# 1_EVB_A32QS1_RFRG_Schematic.net
KiCad netlist of a schematic drawn in Altium Designer
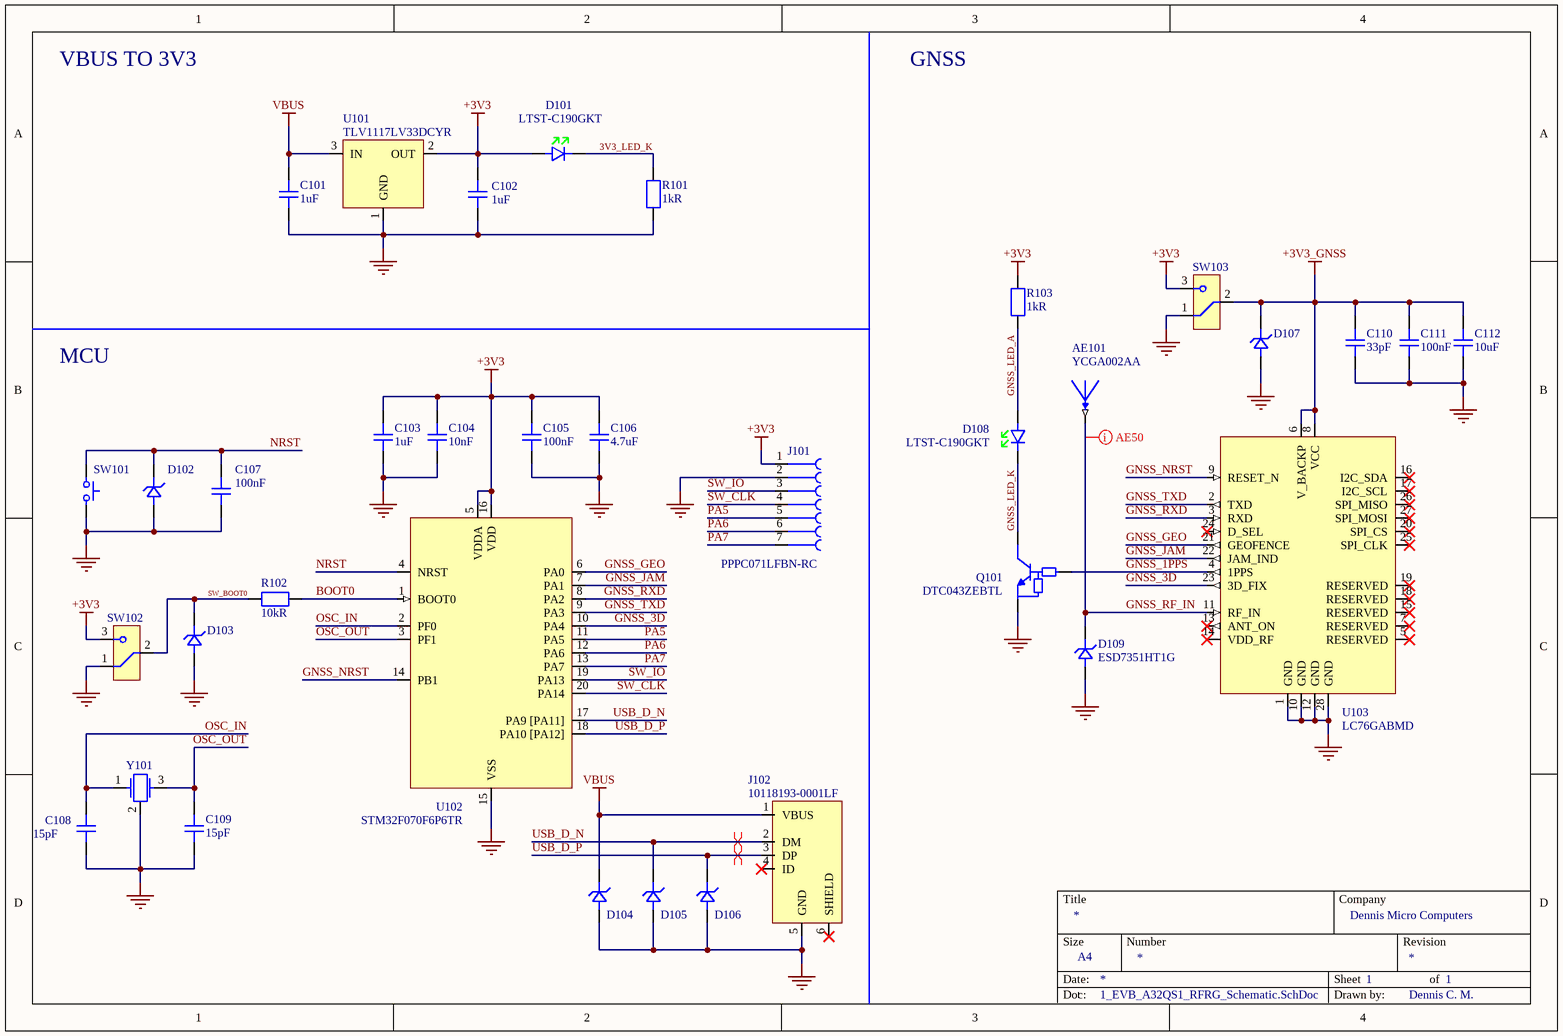
[diagram p0: 1_EVB_A32QS1_RFRG_Schematic.SchDoc]

(export (version "E")
  (design (tool "Eeschema 10.0.6"))
  (components
    (comp (ref "AE101")
      (value "YCGA002AA")
      (footprint "AE_Quectel_YCGA002AA")
      (description "Antenna Module Linear 1602MHz")
      (fields (field (name "MANUFACTURER") "Quectel"))
      (libsource (lib "Dennis Micro Computers") (part "AE_Receiver"))
    )
    (comp (ref "C101")
      (value "1uF")
      (footprint "C_Yageo_CC_0402_A")
      (description "Multilayer Ceramic Capacitor, 1 uF, 50 V, ± 10%, X5R, 0402 [1005 Metric]")
      (fields (field (name "TOLERANCE") "20%") (field (name "LCSC PART NUMBER") "C113791"))
      (libsource (lib "Dennis Micro Computers") (part "C"))
    )
    (comp (ref "C102")
      (value "1uF")
      (footprint "C_Yageo_CC_0402_A")
      (description "Multilayer Ceramic Capacitor, 1 uF, 50 V, ± 10%, X5R, 0402 [1005 Metric]")
      (fields (field (name "TOLERANCE") "20%") (field (name "LCSC PART NUMBER") "C113791"))
      (libsource (lib "Dennis Micro Computers") (part "C"))
    )
    (comp (ref "C103")
      (value "1uF")
      (footprint "C_Yageo_CC_0402_A")
      (description "Multilayer Ceramic Capacitor, 1 uF, 50 V, ± 10%, X5R, 0402 [1005 Metric]")
      (fields (field (name "TOLERANCE") "20%") (field (name "LCSC PART NUMBER") "C113791"))
      (libsource (lib "Dennis Micro Computers") (part "C"))
    )
    (comp (ref "C104")
      (value "10nF")
      (footprint "C_Yageo_CC_0402_A")
      (description "Multilayer Ceramic Capacitor, 0.01 uF, 16 V, ± 10%, X7R, 0402 [1005 Metric]")
      (fields (field (name "TOLERANCE") "10%") (field (name "Comment") "CC0402KRX7R7BB103"))
      (libsource (lib "Dennis Micro Computers") (part "C"))
    )
    (comp (ref "C105")
      (value "100nF")
      (footprint "C_Samsung_CL_0402_A")
      (description "Multilayer Ceramic Capacitor, 0.1 uF, 10 V, ± 10%, X7R, 0402 [1005 Metric]")
      (fields (field (name "TOLERANCE") "10%") (field (name "Comment") "CL05B104KP5NNNC"))
      (libsource (lib "Dennis Micro Computers") (part "C"))
    )
    (comp (ref "C106")
      (value "4.7uF")
      (footprint "C_Samsung_CL_0402_A")
      (description "Multilayer Ceramic Capacitor, 4.7 uF, 10 V, ± 20%, X5R, 0402 [1005 Metric]")
      (fields (field (name "TOLERANCE") "20%") (field (name "Comment") "CL05A475MP5NRNC"))
      (libsource (lib "Dennis Micro Computers") (part "C"))
    )
    (comp (ref "C107")
      (value "100nF")
      (footprint "C_Samsung_CL_0402_A")
      (description "Multilayer Ceramic Capacitor, 0.1 uF, 10 V, ± 10%, X7R, 0402 [1005 Metric]")
      (fields (field (name "TOLERANCE") "10%") (field (name "Comment") "CL05B104KP5NNNC"))
      (libsource (lib "Dennis Micro Computers") (part "C"))
    )
    (comp (ref "C108")
      (value "15pF")
      (footprint "C_Yageo_CC_0402_A")
      (description "Multilayer Ceramic Capacitor, 15 pF, 10 V, ± 5%, X7R, 0402 [1005 Metric]")
      (fields (field (name "TOLERANCE") "5%") (field (name "VOLTAGE") "50V"))
      (libsource (lib "Dennis Micro Computers") (part "C"))
    )
    (comp (ref "C109")
      (value "15pF")
      (footprint "C_Yageo_CC_0402_A")
      (description "Multilayer Ceramic Capacitor, 15 pF, 10 V, ± 5%, X7R, 0402 [1005 Metric]")
      (fields (field (name "TOLERANCE") "5%") (field (name "VOLTAGE") "50V"))
      (libsource (lib "Dennis Micro Computers") (part "C"))
    )
    (comp (ref "C110")
      (value "33pF")
      (footprint "C_Samsung_CL_0402_A")
      (description "Multilayer Ceramic Capacitor, 33 pF, 50 V, ± 5%, C0G (NP0), 0402 [1005 Metric]")
      (fields (field (name "VOLTAGE") "50V") (field (name "TOLERANCE") "5%"))
      (libsource (lib "Dennis Micro Computers") (part "C"))
    )
    (comp (ref "C111")
      (value "100nF")
      (footprint "C_Samsung_CL_0402_A")
      (description "Multilayer Ceramic Capacitor, 0.1 uF, 10 V, ± 10%, X7R, 0402 [1005 Metric]")
      (fields (field (name "TOLERANCE") "10%") (field (name "Comment") "CL05B104KP5NNNC"))
      (libsource (lib "Dennis Micro Computers") (part "C"))
    )
    (comp (ref "C112")
      (value "10uF")
      (footprint "C_Samsung_CL_0805_A")
      (description "Multilayer Ceramic Capacitor, 10 uF, 16 V, ± 10%, X5R, 0805 [2012 Metric]")
      (fields (field (name "TOLERANCE") "10%") (field (name "VOLTAGE") "16V"))
      (libsource (lib "Dennis Micro Computers") (part "C"))
    )
    (comp (ref "D101")
      (value "LTST-C190GKT")
      (footprint "D_LED_Lite-On_Green_0603_A")
      (description "LED Uni-Color Green 565nm 2-Pin Chip LED T/R")
      (fields (field (name "VOLTAGE") "2V"))
      (libsource (lib "Dennis Micro Computers") (part "D_LED_Green"))
    )
    (comp (ref "D102")
      (value "D5V0F1U2S9-7")
      (footprint "D_TVS_Uni_Diodes_SOD-923_B")
      (description "Diode TVS Dual Uni-Dir 5.5V 250000W 2-Pin SOD-923 T/R")
      (libsource (lib "Dennis Micro Computers") (part "D_TVS_Uni"))
    )
    (comp (ref "D103")
      (value "D5V0F1U2S9-7")
      (footprint "D_TVS_Uni_Diodes_SOD-923_B")
      (description "Diode TVS Dual Uni-Dir 5.5V 250000W 2-Pin SOD-923 T/R")
      (libsource (lib "Dennis Micro Computers") (part "D_TVS_Uni"))
    )
    (comp (ref "D104")
      (value "D5V0F1U2S9-7")
      (footprint "D_TVS_Uni_Diodes_SOD-923_B")
      (description "Diode TVS Dual Uni-Dir 5.5V 250000W 2-Pin SOD-923 T/R")
      (libsource (lib "Dennis Micro Computers") (part "D_TVS_Uni"))
    )
    (comp (ref "D105")
      (value "D5V0F1U2S9-7")
      (footprint "D_TVS_Uni_Diodes_SOD-923_B")
      (description "Diode TVS Dual Uni-Dir 5.5V 250000W 2-Pin SOD-923 T/R")
      (libsource (lib "Dennis Micro Computers") (part "D_TVS_Uni"))
    )
    (comp (ref "D106")
      (value "D5V0F1U2S9-7")
      (footprint "D_TVS_Uni_Diodes_SOD-923_B")
      (description "Diode TVS Dual Uni-Dir 5.5V 250000W 2-Pin SOD-923 T/R")
      (libsource (lib "Dennis Micro Computers") (part "D_TVS_Uni"))
    )
    (comp (ref "D107")
      (value "D5V0F1U2S9-7")
      (footprint "D_TVS_Uni_Diodes_SOD-923_B")
      (description "Diode TVS Dual Uni-Dir 5.5V 250000W 2-Pin SOD-923 T/R")
      (libsource (lib "Dennis Micro Computers") (part "D_TVS_Uni"))
    )
    (comp (ref "D108")
      (value "LTST-C190GKT")
      (footprint "D_LED_Lite-On_Green_0603_A")
      (description "LED Uni-Color Green 565nm 2-Pin Chip LED T/R")
      (fields (field (name "VOLTAGE") "2V"))
      (libsource (lib "Dennis Micro Computers") (part "D_LED_Green"))
    )
    (comp (ref "D109")
      (value "ESD7351HT1G")
      (footprint "D_TVS_Uni_Onsemi_SOD-323")
      (description "TVSDIODE3.3VWMSOD-323")
      (libsource (lib "Dennis Micro Computers") (part "D_TVS_Uni"))
    )
    (comp (ref "J101")
      (value "PPPC071LFBN-RC")
      (footprint "J_Sullins_01x07_Socket_2.54mm")
      (description "Conn Hdr 7POS 0.1 Gold Pcb")
      (libsource (lib "Dennis Micro Computers") (part "J_01x07_Socket"))
    )
    (comp (ref "J102")
      (value "10118193-0001LF")
      (footprint "J_USB_Micro-B_Amphenol_10118193-0001LF")
      (description "Usb Connector, 5 Contact(S), Female, Right Angle, Surface Mount Terminal, Locking, Receptacle")
      (libsource (lib "Dennis Micro Computers") (part "J_USB2_B_Micro"))
    )
    (comp (ref "Q101")
      (value "DTC043ZEBTL")
      (footprint "Q_Rohm_SOT-416FL_B")
      (description "TRANS PREBIAS NPN 50V EMT3F")
      (libsource (lib "Dennis Micro Computers") (part "Q_BRT_NPN"))
    )
    (comp (ref "R101")
      (value "1kR")
      (footprint "R_Yageo_RCL_0402_A")
      (description "SMD Chip Resistor, 1 kOhm, ± 1%, 62.5 mW, 0402 [1005 Metric], Thick Film, General Purpose")
      (fields (field (name "TOLERANCE") "1%") (field (name "Comment") "RC0402FR-071KL"))
      (libsource (lib "Dennis Micro Computers") (part "R"))
    )
    (comp (ref "R102")
      (value "10kR")
      (footprint "R_Yageo_RCL_0402_A")
      (description "SMD Chip Resistor, 10 kOhm, ± 1%, 62.5 mW, 0402 [1005 Metric], Thick Film, General Purpose")
      (fields (field (name "TOLERANCE") "1%") (field (name "Comment") "RC0402FR-0710KL"))
      (libsource (lib "Dennis Micro Computers") (part "R"))
    )
    (comp (ref "R103")
      (value "1kR")
      (footprint "R_Yageo_RCL_0402_A")
      (description "SMD Chip Resistor, 1 kOhm, ± 1%, 62.5 mW, 0402 [1005 Metric], Thick Film, General Purpose")
      (fields (field (name "TOLERANCE") "1%") (field (name "Comment") "RC0402FR-071KL"))
      (libsource (lib "Dennis Micro Computers") (part "R"))
    )
    (comp (ref "SW101")
      (value "PTS647SN50SMTR2LFS")
      (footprint "SW_Tactitle_SPST_C&K_PTS647SN50SMTR2LFS")
      (description "Switch Tactile N.O. SPST Round Button Gull Wing 0.05A 12VDC 100000Cycles 0.98N SMD T/R")
      (libsource (lib "Dennis Micro Computers") (part "SW_Tactile_SPST"))
    )
    (comp (ref "SW102")
      (value "JS102011JCQN")
      (footprint "SW_Slide_C&K_JS102011JCQN")
      (description "JS Series Sub-Miniature Slide Switch SPDT On-On Top Slide 0.3A 6VDC J-Lead Surface Mount T/R")
      (libsource (lib "Dennis Micro Computers") (part "SW_Slide_SPDT"))
    )
    (comp (ref "SW103")
      (value "JS102011JCQN")
      (footprint "SW_Slide_C&K_JS102011JCQN")
      (description "JS Series Sub-Miniature Slide Switch SPDT On-On Top Slide 0.3A 6VDC J-Lead Surface Mount T/R")
      (libsource (lib "Dennis Micro Computers") (part "SW_Slide_SPDT"))
    )
    (comp (ref "U101")
      (value "TLV1117LV33DCYR")
      (footprint "U_TI_SOT-223_B")
      (description "LDO Regulator Pos 3.3V 1A 4-Pin(3+Tab) SOT-223 T/R")
      (libsource (lib "Dennis Micro Computers") (part "U_TLV1117LV"))
    )
    (comp (ref "U102")
      (value "STM32F070F6P6TR")
      (footprint "U_ST_TSSOP20_B")
      (description "IC MCU 32BIT 32KB FLASH 20TSSOP")
      (libsource (lib "Dennis Micro Computers") (part "U_STM32F070F6"))
    )
    (comp (ref "U103")
      (value "LC76GABMD")
      (footprint "U_QUECTEL_LC76G")
      (libsource (lib "Dennis Micro Computers") (part "U_LC76G"))
    )
    (comp (ref "Y101")
      (value "ECS-240-12-37B-CKY-TR")
      (footprint "Y_Crystal_GND24_ECS_240-12-37B-CKY-TR")
      (description "Crystal 24MHz ±10ppm (Tol) ±10ppm (Stability) 12pF FUND 50Ohm 4-Pin Mini-CSMD T/R")
      (libsource (lib "Dennis Micro Computers") (part "Y_Crystal_GND24"))
    )
  )
  (nets
    (net (code "1") (name "+3V3") (class "Default")
      (node (ref "C102") (pin "2") (pinfunction "2_2") (pintype "passive"))
      (node (ref "C103") (pin "2") (pinfunction "2_2") (pintype "passive"))
      (node (ref "C104") (pin "2") (pinfunction "2_2") (pintype "passive"))
      (node (ref "C105") (pin "2") (pinfunction "2_2") (pintype "passive"))
      (node (ref "C106") (pin "2") (pinfunction "2_2") (pintype "passive"))
      (node (ref "D101") (pin "2") (pinfunction "2_2") (pintype "passive"))
      (node (ref "J101") (pin "1") (pinfunction "1_1") (pintype "passive"))
      (node (ref "R103") (pin "2") (pinfunction "2_2") (pintype "passive"))
      (node (ref "SW102") (pin "3") (pinfunction "3_3") (pintype "passive"))
      (node (ref "SW103") (pin "3") (pinfunction "3_3") (pintype "passive"))
      (node (ref "U101") (pin "2") (pinfunction "OUT_2") (pintype "power_in"))
      (node (ref "U102") (pin "16") (pinfunction "VDD_16") (pintype "power_in"))
      (node (ref "U102") (pin "5") (pinfunction "VDDA_5") (pintype "power_in"))
    )
    (net (code "2") (name "+3V3_GNSS") (class "Default")
      (node (ref "C110") (pin "2") (pinfunction "2_2") (pintype "passive"))
      (node (ref "C111") (pin "2") (pinfunction "2_2") (pintype "passive"))
      (node (ref "C112") (pin "2") (pinfunction "2_2") (pintype "passive"))
      (node (ref "D107") (pin "1") (pinfunction "1_1") (pintype "passive"))
      (node (ref "SW103") (pin "2") (pinfunction "2_2") (pintype "passive"))
      (node (ref "U103") (pin "6") (pinfunction "V_BACKP_6") (pintype "power_in"))
      (node (ref "U103") (pin "8") (pinfunction "VCC_8") (pintype "power_in"))
    )
    (net (code "3") (name "/3V3_LED_K") (class "Default")
      (node (ref "D101") (pin "1") (pinfunction "1_1") (pintype "passive"))
      (node (ref "R101") (pin "2") (pinfunction "2_2") (pintype "passive"))
    )
    (net (code "4") (name "/BOOT0") (class "Default")
      (node (ref "R102") (pin "2") (pinfunction "2_2") (pintype "passive"))
      (node (ref "U102") (pin "1") (pinfunction "BOOT0_1") (pintype "input"))
    )
    (net (code "5") (name "/GNSS_1PPS") (class "Default")
      (node (ref "Q101") (pin "1") (pinfunction "BASE_1") (pintype "passive"))
      (node (ref "U103") (pin "4") (pinfunction "1PPS_4") (pintype "output"))
    )
    (net (code "6") (name "/GNSS_3D") (class "Default")
      (node (ref "U102") (pin "10") (pinfunction "PA4_10") (pintype "bidirectional"))
      (node (ref "U103") (pin "23") (pinfunction "3D_FIX_23") (pintype "output"))
    )
    (net (code "7") (name "/GNSS_GEO") (class "Default")
      (node (ref "U102") (pin "6") (pinfunction "PA0_6") (pintype "bidirectional"))
      (node (ref "U103") (pin "21") (pinfunction "GEOFENCE_21") (pintype "output"))
    )
    (net (code "8") (name "/GNSS_JAM") (class "Default")
      (node (ref "U102") (pin "7") (pinfunction "PA1_7") (pintype "bidirectional"))
      (node (ref "U103") (pin "22") (pinfunction "JAM_IND_22") (pintype "output"))
    )
    (net (code "9") (name "/GNSS_LED_A") (class "Default")
      (node (ref "D108") (pin "2") (pinfunction "2_2") (pintype "passive"))
      (node (ref "R103") (pin "1") (pinfunction "1_1") (pintype "passive"))
    )
    (net (code "10") (name "/GNSS_LED_K") (class "Default")
      (node (ref "D108") (pin "1") (pinfunction "1_1") (pintype "passive"))
      (node (ref "Q101") (pin "3") (pinfunction "COLLECTOR_3") (pintype "passive"))
    )
    (net (code "11") (name "/GNSS_NRST") (class "Default")
      (node (ref "U102") (pin "14") (pinfunction "PB1_14") (pintype "bidirectional"))
      (node (ref "U103") (pin "9") (pinfunction "RESET_N_9") (pintype "input"))
    )
    (net (code "12") (name "/GNSS_RF_IN") (class "Default")
      (node (ref "AE101") (pin "1") (pinfunction "1_1") (pintype "output"))
      (node (ref "D109") (pin "1") (pinfunction "1_1") (pintype "passive"))
      (node (ref "U103") (pin "11") (pinfunction "RF_IN_11") (pintype "input"))
    )
    (net (code "13") (name "/GNSS_RXD") (class "Default")
      (node (ref "U102") (pin "8") (pinfunction "PA2_8") (pintype "bidirectional"))
      (node (ref "U103") (pin "3") (pinfunction "RXD_3") (pintype "input"))
    )
    (net (code "14") (name "/GNSS_TXD") (class "Default")
      (node (ref "U102") (pin "9") (pinfunction "PA3_9") (pintype "bidirectional"))
      (node (ref "U103") (pin "2") (pinfunction "TXD_2") (pintype "output"))
    )
    (net (code "15") (name "/NRST") (class "Default")
      (node (ref "C107") (pin "2") (pinfunction "2_2") (pintype "passive"))
      (node (ref "D102") (pin "1") (pinfunction "1_1") (pintype "passive"))
      (node (ref "SW101") (pin "1") (pinfunction "1_1") (pintype "passive"))
      (node (ref "U102") (pin "4") (pinfunction "NRST_4") (pintype "bidirectional"))
    )
    (net (code "16") (name "/OSC_IN") (class "Default")
      (node (ref "C108") (pin "2") (pinfunction "2_2") (pintype "passive"))
      (node (ref "U102") (pin "2") (pinfunction "PF0_2") (pintype "bidirectional"))
      (node (ref "Y101") (pin "1") (pinfunction "1_1") (pintype "passive"))
    )
    (net (code "17") (name "/OSC_OUT") (class "Default")
      (node (ref "C109") (pin "2") (pinfunction "2_2") (pintype "passive"))
      (node (ref "U102") (pin "3") (pinfunction "PF1_3") (pintype "bidirectional"))
      (node (ref "Y101") (pin "3") (pinfunction "3_3") (pintype "passive"))
    )
    (net (code "18") (name "/PA5") (class "Default")
      (node (ref "J101") (pin "5") (pinfunction "5_5") (pintype "passive"))
      (node (ref "U102") (pin "11") (pinfunction "PA5_11") (pintype "bidirectional"))
    )
    (net (code "19") (name "/PA6") (class "Default")
      (node (ref "J101") (pin "6") (pinfunction "6_6") (pintype "passive"))
      (node (ref "U102") (pin "12") (pinfunction "PA6_12") (pintype "bidirectional"))
    )
    (net (code "20") (name "/PA7") (class "Default")
      (node (ref "J101") (pin "7") (pinfunction "7_7") (pintype "passive"))
      (node (ref "U102") (pin "13") (pinfunction "PA7_13") (pintype "bidirectional"))
    )
    (net (code "21") (name "/SW_BOOT0") (class "Default")
      (node (ref "D103") (pin "1") (pinfunction "1_1") (pintype "passive"))
      (node (ref "R102") (pin "1") (pinfunction "1_1") (pintype "passive"))
      (node (ref "SW102") (pin "2") (pinfunction "2_2") (pintype "passive"))
    )
    (net (code "22") (name "/SW_CLK") (class "Default")
      (node (ref "J101") (pin "4") (pinfunction "4_4") (pintype "passive"))
      (node (ref "U102") (pin "20") (pinfunction "PA14_20") (pintype "bidirectional"))
    )
    (net (code "23") (name "/SW_IO") (class "Default")
      (node (ref "J101") (pin "3") (pinfunction "3_3") (pintype "passive"))
      (node (ref "U102") (pin "19") (pinfunction "PA13_19") (pintype "bidirectional"))
    )
    (net (code "24") (name "/USB_D_N") (class "Default")
      (node (ref "D105") (pin "1") (pinfunction "1_1") (pintype "passive"))
      (node (ref "J102") (pin "2") (pinfunction "DM_2") (pintype "bidirectional"))
      (node (ref "U102") (pin "17") (pinfunction "PA9_[PA11]_17") (pintype "bidirectional"))
    )
    (net (code "25") (name "/USB_D_P") (class "Default")
      (node (ref "D106") (pin "1") (pinfunction "1_1") (pintype "passive"))
      (node (ref "J102") (pin "3") (pinfunction "DP_3") (pintype "bidirectional"))
      (node (ref "U102") (pin "18") (pinfunction "PA10_[PA12]_18") (pintype "bidirectional"))
    )
    (net (code "26") (name "GND") (class "Default")
      (node (ref "C101") (pin "1") (pinfunction "1_1") (pintype "passive"))
      (node (ref "C102") (pin "1") (pinfunction "1_1") (pintype "passive"))
      (node (ref "C103") (pin "1") (pinfunction "1_1") (pintype "passive"))
      (node (ref "C104") (pin "1") (pinfunction "1_1") (pintype "passive"))
      (node (ref "C105") (pin "1") (pinfunction "1_1") (pintype "passive"))
      (node (ref "C106") (pin "1") (pinfunction "1_1") (pintype "passive"))
      (node (ref "C107") (pin "1") (pinfunction "1_1") (pintype "passive"))
      (node (ref "C108") (pin "1") (pinfunction "1_1") (pintype "passive"))
      (node (ref "C109") (pin "1") (pinfunction "1_1") (pintype "passive"))
      (node (ref "C110") (pin "1") (pinfunction "1_1") (pintype "passive"))
      (node (ref "C111") (pin "1") (pinfunction "1_1") (pintype "passive"))
      (node (ref "C112") (pin "1") (pinfunction "1_1") (pintype "passive"))
      (node (ref "D102") (pin "2") (pinfunction "2_2") (pintype "passive"))
      (node (ref "D103") (pin "2") (pinfunction "2_2") (pintype "passive"))
      (node (ref "D104") (pin "2") (pinfunction "2_2") (pintype "passive"))
      (node (ref "D105") (pin "2") (pinfunction "2_2") (pintype "passive"))
      (node (ref "D106") (pin "2") (pinfunction "2_2") (pintype "passive"))
      (node (ref "D107") (pin "2") (pinfunction "2_2") (pintype "passive"))
      (node (ref "D109") (pin "2") (pinfunction "2_2") (pintype "passive"))
      (node (ref "J101") (pin "2") (pinfunction "2_2") (pintype "passive"))
      (node (ref "J102") (pin "5") (pinfunction "GND_5") (pintype "power_in"))
      (node (ref "Q101") (pin "2") (pinfunction "EMITTER_2") (pintype "passive"))
      (node (ref "R101") (pin "1") (pinfunction "1_1") (pintype "passive"))
      (node (ref "SW101") (pin "2") (pinfunction "2_2") (pintype "passive"))
      (node (ref "SW102") (pin "1") (pinfunction "1_1") (pintype "passive"))
      (node (ref "SW103") (pin "1") (pinfunction "1_1") (pintype "passive"))
      (node (ref "U101") (pin "1") (pinfunction "GND_1") (pintype "power_in"))
      (node (ref "U102") (pin "15") (pinfunction "VSS_15") (pintype "power_in"))
      (node (ref "U103") (pin "1") (pinfunction "GND_1") (pintype "power_in"))
      (node (ref "U103") (pin "10") (pinfunction "GND_10") (pintype "power_in"))
      (node (ref "U103") (pin "12") (pinfunction "GND_12") (pintype "power_in"))
      (node (ref "U103") (pin "28") (pinfunction "GND_28") (pintype "power_in"))
      (node (ref "Y101") (pin "2") (pinfunction "2_2") (pintype "passive"))
    )
    (net (code "27") (name "VBUS") (class "Default")
      (node (ref "C101") (pin "2") (pinfunction "2_2") (pintype "passive"))
      (node (ref "D104") (pin "1") (pinfunction "1_1") (pintype "passive"))
      (node (ref "J102") (pin "1") (pinfunction "VBUS_1") (pintype "power_in"))
      (node (ref "U101") (pin "3") (pinfunction "IN_3") (pintype "power_in"))
    )
    (net (code "28") (name "unconnected-(J102-ID-Pad4)") (class "Default")
      (node (ref "J102") (pin "4") (pinfunction "ID_4") (pintype "passive+no_connect"))
    )
    (net (code "29") (name "unconnected-(J102-SHIELD-Pad6)") (class "Default")
      (node (ref "J102") (pin "6") (pinfunction "SHIELD_6") (pintype "passive+no_connect"))
    )
    (net (code "30") (name "unconnected-(U103-ANT_ON-Pad13)") (class "Default")
      (node (ref "U103") (pin "13") (pinfunction "ANT_ON_13") (pintype "output+no_connect"))
    )
    (net (code "31") (name "unconnected-(U103-D_SEL-Pad24)") (class "Default")
      (node (ref "U103") (pin "24") (pinfunction "D_SEL_24") (pintype "input+no_connect"))
    )
    (net (code "32") (name "unconnected-(U103-I2C_SCL-Pad17)") (class "Default")
      (node (ref "U103") (pin "17") (pinfunction "I2C_SCL_17") (pintype "bidirectional+no_connect"))
    )
    (net (code "33") (name "unconnected-(U103-I2C_SDA-Pad16)") (class "Default")
      (node (ref "U103") (pin "16") (pinfunction "I2C_SDA_16") (pintype "bidirectional+no_connect"))
    )
    (net (code "34") (name "unconnected-(U103-RESERVED-Pad5)") (class "Default")
      (node (ref "U103") (pin "5") (pinfunction "RESERVED_5") (pintype "passive+no_connect"))
    )
    (net (code "35") (name "unconnected-(U103-RESERVED-Pad7)") (class "Default")
      (node (ref "U103") (pin "7") (pinfunction "RESERVED_7") (pintype "passive+no_connect"))
    )
    (net (code "36") (name "unconnected-(U103-RESERVED-Pad15)") (class "Default")
      (node (ref "U103") (pin "15") (pinfunction "RESERVED_15") (pintype "passive+no_connect"))
    )
    (net (code "37") (name "unconnected-(U103-RESERVED-Pad18)") (class "Default")
      (node (ref "U103") (pin "18") (pinfunction "RESERVED_18") (pintype "passive+no_connect"))
    )
    (net (code "38") (name "unconnected-(U103-RESERVED-Pad19)") (class "Default")
      (node (ref "U103") (pin "19") (pinfunction "RESERVED_19") (pintype "passive+no_connect"))
    )
    (net (code "39") (name "unconnected-(U103-SPI_CLK-Pad25)") (class "Default")
      (node (ref "U103") (pin "25") (pinfunction "SPI_CLK_25") (pintype "bidirectional+no_connect"))
    )
    (net (code "40") (name "unconnected-(U103-SPI_CS-Pad20)") (class "Default")
      (node (ref "U103") (pin "20") (pinfunction "SPI_CS_20") (pintype "bidirectional+no_connect"))
    )
    (net (code "41") (name "unconnected-(U103-SPI_MISO-Pad26)") (class "Default")
      (node (ref "U103") (pin "26") (pinfunction "SPI_MISO_26") (pintype "bidirectional+no_connect"))
    )
    (net (code "42") (name "unconnected-(U103-SPI_MOSI-Pad27)") (class "Default")
      (node (ref "U103") (pin "27") (pinfunction "SPI_MOSI_27") (pintype "bidirectional+no_connect"))
    )
    (net (code "43") (name "unconnected-(U103-VDD_RF-Pad14)") (class "Default")
      (node (ref "U103") (pin "14") (pinfunction "VDD_RF_14") (pintype "power_in+no_connect"))
    )
  )
)
